# battery_powered_devel_board.net
KiCad netlist of a schematic drawn in EAGLE
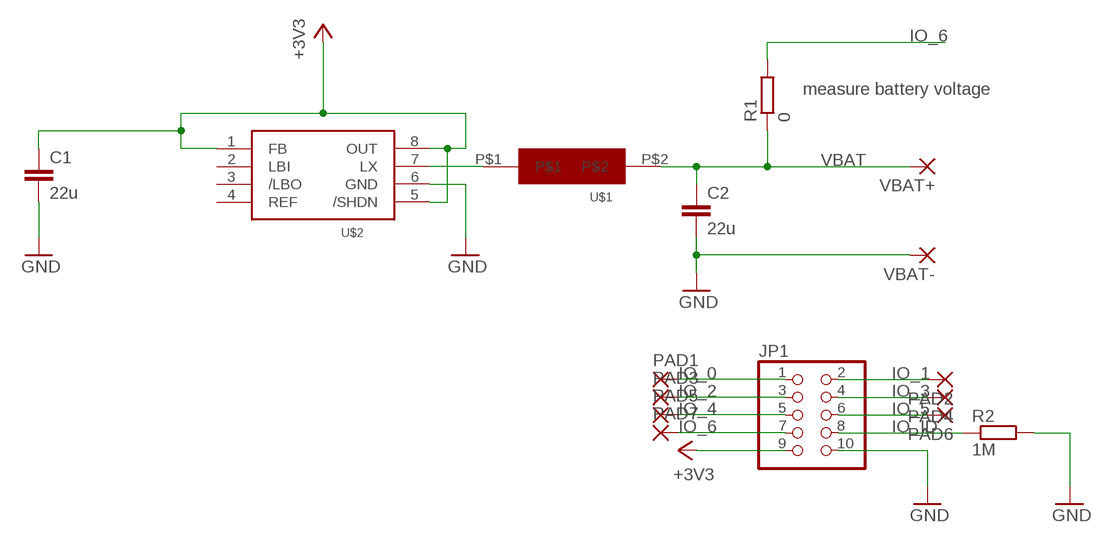
[diagram p0: schematic, sheet 1]

(export (version "E")
  (design (tool "Eeschema 10.0.6"))
  (components
    (comp (ref "C1")
      (value "22u")
      (footprint "eagle-import:C0805")
      (libsource (lib "eagle-import") (part "C-EUC0805"))
    )
    (comp (ref "C2")
      (value "22u")
      (footprint "eagle-import:C0805")
      (libsource (lib "eagle-import") (part "C-EUC0805"))
    )
    (comp (ref "JP1")
      (value "PINHD-2X5")
      (footprint "eagle-import:2X05")
      (libsource (lib "eagle-import") (part "PINHD-2X5"))
    )
    (comp (ref "PAD1")
      (value "1,6/0,8")
      (footprint "eagle-import:1,6_0,8")
      (libsource (lib "eagle-import") (part "1,6/0,8"))
    )
    (comp (ref "PAD2")
      (value "1,6/0,8")
      (footprint "eagle-import:1,6_0,8")
      (libsource (lib "eagle-import") (part "1,6/0,8"))
    )
    (comp (ref "PAD3")
      (value "1,6/0,8")
      (footprint "eagle-import:1,6_0,8")
      (libsource (lib "eagle-import") (part "1,6/0,8"))
    )
    (comp (ref "PAD4")
      (value "1,6/0,8")
      (footprint "eagle-import:1,6_0,8")
      (libsource (lib "eagle-import") (part "1,6/0,8"))
    )
    (comp (ref "PAD5")
      (value "1,6/0,8")
      (footprint "eagle-import:1,6_0,8")
      (libsource (lib "eagle-import") (part "1,6/0,8"))
    )
    (comp (ref "PAD6")
      (value "1,6/0,8")
      (footprint "eagle-import:1,6_0,8")
      (libsource (lib "eagle-import") (part "1,6/0,8"))
    )
    (comp (ref "PAD7")
      (value "1,6/0,8")
      (footprint "eagle-import:1,6_0,8")
      (libsource (lib "eagle-import") (part "1,6/0,8"))
    )
    (comp (ref "R1")
      (value "0")
      (footprint "eagle-import:R0402")
      (libsource (lib "eagle-import") (part "R-EU_R0402"))
    )
    (comp (ref "R2")
      (value "1M")
      (footprint "eagle-import:R0402")
      (libsource (lib "eagle-import") (part "R-EU_R0402"))
    )
    (comp (ref "U$1")
      (value "ELL_INDUCTOR")
      (footprint "eagle-import:ELL6_INDUCTOR")
      (libsource (lib "eagle-import") (part "ELL_INDUCTOR"))
    )
    (comp (ref "U$2")
      (value "L6920")
      (footprint "eagle-import:TSSOP8")
      (libsource (lib "eagle-import") (part "L6920"))
    )
    (comp (ref "VBAT+")
      (value "2,54/1,0")
      (footprint "eagle-import:2,54_1,0")
      (libsource (lib "eagle-import") (part "2,54/1,0"))
    )
    (comp (ref "VBAT-")
      (value "2,54/1,0")
      (footprint "eagle-import:2,54_1,0")
      (libsource (lib "eagle-import") (part "2,54/1,0"))
    )
  )
  (nets
    (net (code "1") (name "+3V3") (class "Default")
      (node (ref "C1") (pin "1") (pinfunction "1_1") (pintype "passive"))
      (node (ref "JP1") (pin "9") (pinfunction "9_9") (pintype "passive"))
      (node (ref "U$2") (pin "1") (pinfunction "FB_1") (pintype "bidirectional"))
      (node (ref "U$2") (pin "5") (pinfunction "/SHDN_5") (pintype "bidirectional"))
      (node (ref "U$2") (pin "8") (pinfunction "OUT_8") (pintype "bidirectional"))
    )
    (net (code "2") (name "/IO_0") (class "Default")
      (node (ref "JP1") (pin "1") (pinfunction "1_1") (pintype "passive"))
      (node (ref "PAD1") (pin "1") (pinfunction "P_1") (pintype "passive"))
    )
    (net (code "3") (name "/IO_1") (class "Default")
      (node (ref "JP1") (pin "2") (pinfunction "2_2") (pintype "passive"))
      (node (ref "PAD2") (pin "1") (pinfunction "P_1") (pintype "passive"))
    )
    (net (code "4") (name "/IO_2") (class "Default")
      (node (ref "JP1") (pin "3") (pinfunction "3_3") (pintype "passive"))
      (node (ref "PAD3") (pin "1") (pinfunction "P_1") (pintype "passive"))
    )
    (net (code "5") (name "/IO_3") (class "Default")
      (node (ref "JP1") (pin "4") (pinfunction "4_4") (pintype "passive"))
      (node (ref "PAD4") (pin "1") (pinfunction "P_1") (pintype "passive"))
    )
    (net (code "6") (name "/IO_4") (class "Default")
      (node (ref "JP1") (pin "5") (pinfunction "5_5") (pintype "passive"))
      (node (ref "PAD5") (pin "1") (pinfunction "P_1") (pintype "passive"))
    )
    (net (code "7") (name "/IO_5") (class "Default")
      (node (ref "JP1") (pin "6") (pinfunction "6_6") (pintype "passive"))
      (node (ref "PAD6") (pin "1") (pinfunction "P_1") (pintype "passive"))
    )
    (net (code "8") (name "/IO_6") (class "Default")
      (node (ref "JP1") (pin "7") (pinfunction "7_7") (pintype "passive"))
      (node (ref "PAD7") (pin "1") (pinfunction "P_1") (pintype "passive"))
      (node (ref "R1") (pin "2") (pinfunction "2_2") (pintype "passive"))
    )
    (net (code "9") (name "/IO_ID") (class "Default")
      (node (ref "JP1") (pin "8") (pinfunction "8_8") (pintype "passive"))
      (node (ref "R2") (pin "1") (pinfunction "1_1") (pintype "passive"))
    )
    (net (code "10") (name "/VBAT") (class "Default")
      (node (ref "C2") (pin "1") (pinfunction "1_1") (pintype "passive"))
      (node (ref "R1") (pin "1") (pinfunction "1_1") (pintype "passive"))
      (node (ref "U$1") (pin "P$2") (pinfunction "P$2_P$2") (pintype "bidirectional"))
      (node (ref "VBAT+") (pin "1") (pinfunction "P_1") (pintype "passive"))
    )
    (net (code "11") (name "GND") (class "Default")
      (node (ref "C1") (pin "2") (pinfunction "2_2") (pintype "passive"))
      (node (ref "C2") (pin "2") (pinfunction "2_2") (pintype "passive"))
      (node (ref "JP1") (pin "10") (pinfunction "10_10") (pintype "passive"))
      (node (ref "R2") (pin "2") (pinfunction "2_2") (pintype "passive"))
      (node (ref "U$2") (pin "6") (pinfunction "GND_6") (pintype "bidirectional"))
      (node (ref "VBAT-") (pin "1") (pinfunction "P_1") (pintype "passive"))
    )
    (net (code "12") (name "Net-(U$2-LX)") (class "Default")
      (node (ref "U$1") (pin "P$1") (pinfunction "P$1_P$1") (pintype "bidirectional"))
      (node (ref "U$2") (pin "7") (pinfunction "LX_7") (pintype "bidirectional"))
    )
    (net (code "13") (name "unconnected-(U$2-LBI-Pad2)") (class "Default")
      (node (ref "U$2") (pin "2") (pinfunction "LBI_2") (pintype "bidirectional"))
    )
    (net (code "14") (name "unconnected-(U$2-REF-Pad4)") (class "Default")
      (node (ref "U$2") (pin "4") (pinfunction "REF_4") (pintype "bidirectional"))
    )
    (net (code "15") (name "unconnected-(U$2-{slash}LBO-Pad3)") (class "Default")
      (node (ref "U$2") (pin "3") (pinfunction "/LBO_3") (pintype "bidirectional"))
    )
  )
)
